# test_baro_24.net
KiCad netlist of a schematic drawn in EAGLE
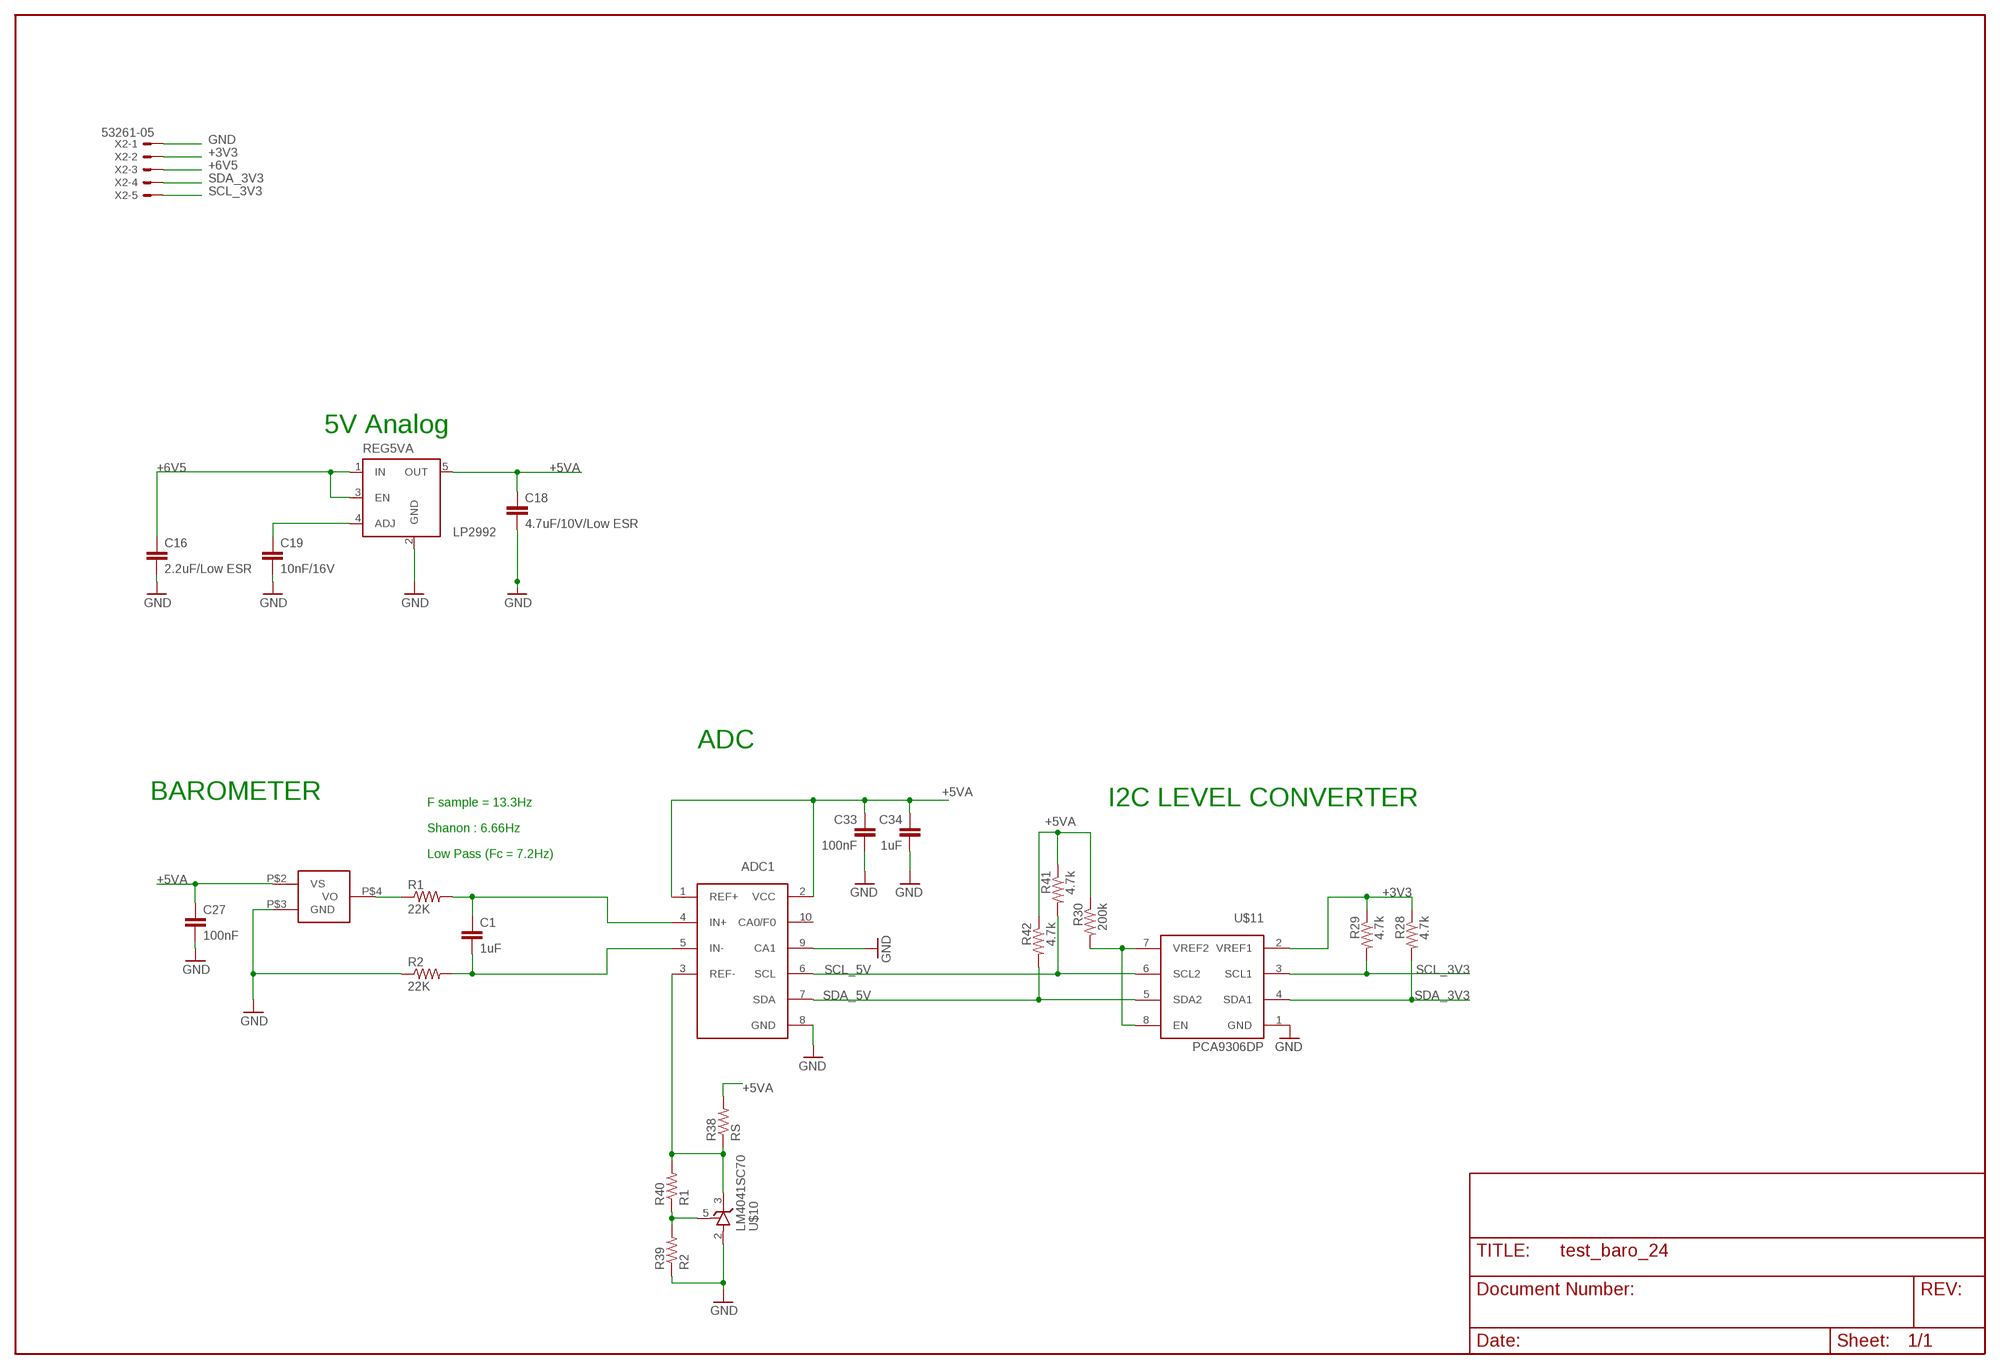
[diagram p0: schematic, sheet 1]

(export (version "E")
  (design (tool "Eeschema 10.0.6"))
  (components
    (comp (ref "ADC1")
      (value "LTC2485")
      (footprint "eagle-import:DFN10")
      (libsource (lib "eagle-import") (part "LTC2485"))
    )
    (comp (ref "C1")
      (value "1uF")
      (footprint "eagle-import:C1206K")
      (libsource (lib "eagle-import") (part "C-EUC1206K"))
    )
    (comp (ref "C16")
      (value "2.2uF/Low ESR")
      (footprint "eagle-import:C0603")
      (libsource (lib "eagle-import") (part "C-EUC0603"))
    )
    (comp (ref "C18")
      (value "4.7uF/10V/Low ESR")
      (footprint "eagle-import:C0805K")
      (libsource (lib "eagle-import") (part "C-EUC0805K"))
    )
    (comp (ref "C19")
      (value "10nF/16V")
      (footprint "eagle-import:C0603K")
      (libsource (lib "eagle-import") (part "C-EUC0603K"))
    )
    (comp (ref "C27")
      (value "100nF")
      (footprint "eagle-import:C0603")
      (libsource (lib "eagle-import") (part "C-EUC0603"))
    )
    (comp (ref "C33")
      (value "100nF")
      (footprint "eagle-import:C0603")
      (libsource (lib "eagle-import") (part "C-EUC0603"))
    )
    (comp (ref "C34")
      (value "1uF")
      (footprint "eagle-import:C0805")
      (libsource (lib "eagle-import") (part "C-EUC0805"))
    )
    (comp (ref "R1")
      (value "22K")
      (footprint "eagle-import:R0603")
      (libsource (lib "eagle-import") (part "R-US_R0603"))
    )
    (comp (ref "R2")
      (value "22K")
      (footprint "eagle-import:R0603")
      (libsource (lib "eagle-import") (part "R-US_R0603"))
    )
    (comp (ref "R28")
      (value "4.7k")
      (footprint "eagle-import:R0603")
      (libsource (lib "eagle-import") (part "R-US_R0603"))
    )
    (comp (ref "R29")
      (value "4.7k")
      (footprint "eagle-import:R0603")
      (libsource (lib "eagle-import") (part "R-US_R0603"))
    )
    (comp (ref "R30")
      (value "200k")
      (footprint "eagle-import:R0603")
      (libsource (lib "eagle-import") (part "R-US_R0603"))
    )
    (comp (ref "R38")
      (value "RS")
      (footprint "eagle-import:R0603")
      (libsource (lib "eagle-import") (part "R-US_R0603"))
    )
    (comp (ref "R39")
      (value "R2")
      (footprint "eagle-import:R0603")
      (libsource (lib "eagle-import") (part "R-US_R0603"))
    )
    (comp (ref "R40")
      (value "R1")
      (footprint "eagle-import:R0603")
      (libsource (lib "eagle-import") (part "R-US_R0603"))
    )
    (comp (ref "R41")
      (value "4.7k")
      (footprint "eagle-import:R0603")
      (libsource (lib "eagle-import") (part "R-US_R0603"))
    )
    (comp (ref "R42")
      (value "4.7k")
      (footprint "eagle-import:R0603")
      (libsource (lib "eagle-import") (part "R-US_R0603"))
    )
    (comp (ref "REG5VA")
      (value "LP2992")
      (footprint "eagle-import:SOT23-5")
      (libsource (lib "eagle-import") (part "MIC5219BM5"))
    )
    (comp (ref "U$2")
      (value "MPX6115")
      (footprint "eagle-import:CASE_1317")
      (libsource (lib "eagle-import") (part "MPX6115"))
    )
    (comp (ref "U$10")
      (value "LM4041SC70")
      (footprint "eagle-import:SC70-5L")
      (libsource (lib "eagle-import") (part "LM4041SC70"))
    )
    (comp (ref "U$11")
      (value "PCA9306DP")
      (footprint "eagle-import:TSSOP_B3")
      (libsource (lib "eagle-import") (part "PCA9306DP"))
    )
    (comp (ref "X2")
      (value "53261-05")
      (footprint "eagle-import:53261-05")
      (libsource (lib "eagle-import") (part "53?-05261"))
    )
  )
  (nets
    (net (code "1") (name "/+3V3") (class "Default")
      (node (ref "R28") (pin "1") (pinfunction "1_1") (pintype "passive"))
      (node (ref "R29") (pin "1") (pinfunction "1_1") (pintype "passive"))
      (node (ref "U$11") (pin "2") (pinfunction "VREF1_2") (pintype "bidirectional"))
      (node (ref "X2") (pin "2") (pinfunction "S_2") (pintype "passive"))
    )
    (net (code "2") (name "/+5VA") (class "Default")
      (node (ref "ADC1") (pin "1") (pinfunction "REF+_1") (pintype "bidirectional"))
      (node (ref "ADC1") (pin "2") (pinfunction "VCC_2") (pintype "bidirectional"))
      (node (ref "C18") (pin "1") (pinfunction "1_1") (pintype "passive"))
      (node (ref "C27") (pin "1") (pinfunction "1_1") (pintype "passive"))
      (node (ref "C33") (pin "1") (pinfunction "1_1") (pintype "passive"))
      (node (ref "C34") (pin "1") (pinfunction "1_1") (pintype "passive"))
      (node (ref "R30") (pin "1") (pinfunction "1_1") (pintype "passive"))
      (node (ref "R38") (pin "2") (pinfunction "2_2") (pintype "passive"))
      (node (ref "R41") (pin "1") (pinfunction "1_1") (pintype "passive"))
      (node (ref "R42") (pin "1") (pinfunction "1_1") (pintype "passive"))
      (node (ref "REG5VA") (pin "5") (pinfunction "OUT_5") (pintype "output"))
      (node (ref "U$2") (pin "P$2") (pinfunction "VS_P$2") (pintype "bidirectional"))
    )
    (net (code "3") (name "/+6V5") (class "Default")
      (node (ref "C16") (pin "1") (pinfunction "1_1") (pintype "passive"))
      (node (ref "REG5VA") (pin "1") (pinfunction "IN_1") (pintype "input"))
      (node (ref "REG5VA") (pin "3") (pinfunction "EN_3") (pintype "input"))
      (node (ref "X2") (pin "3") (pinfunction "S_3") (pintype "passive"))
    )
    (net (code "4") (name "/SCL_3V3") (class "Default")
      (node (ref "R29") (pin "2") (pinfunction "2_2") (pintype "passive"))
      (node (ref "U$11") (pin "3") (pinfunction "SCL1_3") (pintype "bidirectional"))
      (node (ref "X2") (pin "5") (pinfunction "S_5") (pintype "passive"))
    )
    (net (code "5") (name "/SCL_5V") (class "Default")
      (node (ref "ADC1") (pin "6") (pinfunction "SCL_6") (pintype "bidirectional"))
      (node (ref "R41") (pin "2") (pinfunction "2_2") (pintype "passive"))
      (node (ref "U$11") (pin "6") (pinfunction "SCL2_6") (pintype "bidirectional"))
    )
    (net (code "6") (name "/SDA_3V3") (class "Default")
      (node (ref "R28") (pin "2") (pinfunction "2_2") (pintype "passive"))
      (node (ref "U$11") (pin "4") (pinfunction "SDA1_4") (pintype "bidirectional"))
      (node (ref "X2") (pin "4") (pinfunction "S_4") (pintype "passive"))
    )
    (net (code "7") (name "/SDA_5V") (class "Default")
      (node (ref "ADC1") (pin "7") (pinfunction "SDA_7") (pintype "bidirectional"))
      (node (ref "R42") (pin "2") (pinfunction "2_2") (pintype "passive"))
      (node (ref "U$11") (pin "5") (pinfunction "SDA2_5") (pintype "bidirectional"))
    )
    (net (code "8") (name "GND") (class "Default")
      (node (ref "ADC1") (pin "8") (pinfunction "GND_8") (pintype "bidirectional"))
      (node (ref "ADC1") (pin "9") (pinfunction "CA1_9") (pintype "bidirectional"))
      (node (ref "C16") (pin "2") (pinfunction "2_2") (pintype "passive"))
      (node (ref "C18") (pin "2") (pinfunction "2_2") (pintype "passive"))
      (node (ref "C19") (pin "2") (pinfunction "2_2") (pintype "passive"))
      (node (ref "C27") (pin "2") (pinfunction "2_2") (pintype "passive"))
      (node (ref "C33") (pin "2") (pinfunction "2_2") (pintype "passive"))
      (node (ref "C34") (pin "2") (pinfunction "2_2") (pintype "passive"))
      (node (ref "R2") (pin "1") (pinfunction "1_1") (pintype "passive"))
      (node (ref "R39") (pin "1") (pinfunction "1_1") (pintype "passive"))
      (node (ref "REG5VA") (pin "2") (pinfunction "GND_2") (pintype "power_in"))
      (node (ref "U$10") (pin "2") (pinfunction "A_2") (pintype "passive"))
      (node (ref "U$11") (pin "1") (pinfunction "GND_1") (pintype "bidirectional"))
      (node (ref "U$2") (pin "P$3") (pinfunction "GND_P$3") (pintype "bidirectional"))
      (node (ref "X2") (pin "1") (pinfunction "S_1") (pintype "passive"))
    )
    (net (code "9") (name "Net-(ADC1-IN+)") (class "Default")
      (node (ref "ADC1") (pin "4") (pinfunction "IN+_4") (pintype "bidirectional"))
      (node (ref "C1") (pin "1") (pinfunction "1_1") (pintype "passive"))
      (node (ref "R1") (pin "2") (pinfunction "2_2") (pintype "passive"))
    )
    (net (code "10") (name "Net-(ADC1-IN-)") (class "Default")
      (node (ref "ADC1") (pin "5") (pinfunction "IN-_5") (pintype "bidirectional"))
      (node (ref "C1") (pin "2") (pinfunction "2_2") (pintype "passive"))
      (node (ref "R2") (pin "2") (pinfunction "2_2") (pintype "passive"))
    )
    (net (code "11") (name "Net-(ADC1-REF-)") (class "Default")
      (node (ref "ADC1") (pin "3") (pinfunction "REF-_3") (pintype "bidirectional"))
      (node (ref "R38") (pin "1") (pinfunction "1_1") (pintype "passive"))
      (node (ref "R40") (pin "2") (pinfunction "2_2") (pintype "passive"))
      (node (ref "U$10") (pin "3") (pinfunction "C_3") (pintype "passive"))
    )
    (net (code "12") (name "Net-(REG5VA-ADJ)") (class "Default")
      (node (ref "C19") (pin "1") (pinfunction "1_1") (pintype "passive"))
      (node (ref "REG5VA") (pin "4") (pinfunction "ADJ_4") (pintype "passive"))
    )
    (net (code "13") (name "Net-(U$2-VO)") (class "Default")
      (node (ref "R1") (pin "1") (pinfunction "1_1") (pintype "passive"))
      (node (ref "U$2") (pin "P$4") (pinfunction "VO_P$4") (pintype "bidirectional"))
    )
    (net (code "14") (name "Net-(U$10-R)") (class "Default")
      (node (ref "R39") (pin "2") (pinfunction "2_2") (pintype "passive"))
      (node (ref "R40") (pin "1") (pinfunction "1_1") (pintype "passive"))
      (node (ref "U$10") (pin "5") (pinfunction "R_5") (pintype "passive"))
    )
    (net (code "15") (name "Net-(U$11-EN)") (class "Default")
      (node (ref "R30") (pin "2") (pinfunction "2_2") (pintype "passive"))
      (node (ref "U$11") (pin "7") (pinfunction "VREF2_7") (pintype "bidirectional"))
      (node (ref "U$11") (pin "8") (pinfunction "EN_8") (pintype "bidirectional"))
    )
    (net (code "16") (name "unconnected-(ADC1-CA0{slash}F0-Pad10)") (class "Default")
      (node (ref "ADC1") (pin "10") (pinfunction "CA0/F0_10") (pintype "bidirectional"))
    )
  )
)
